# standalone.net
KiCad netlist of a schematic drawn in EAGLE
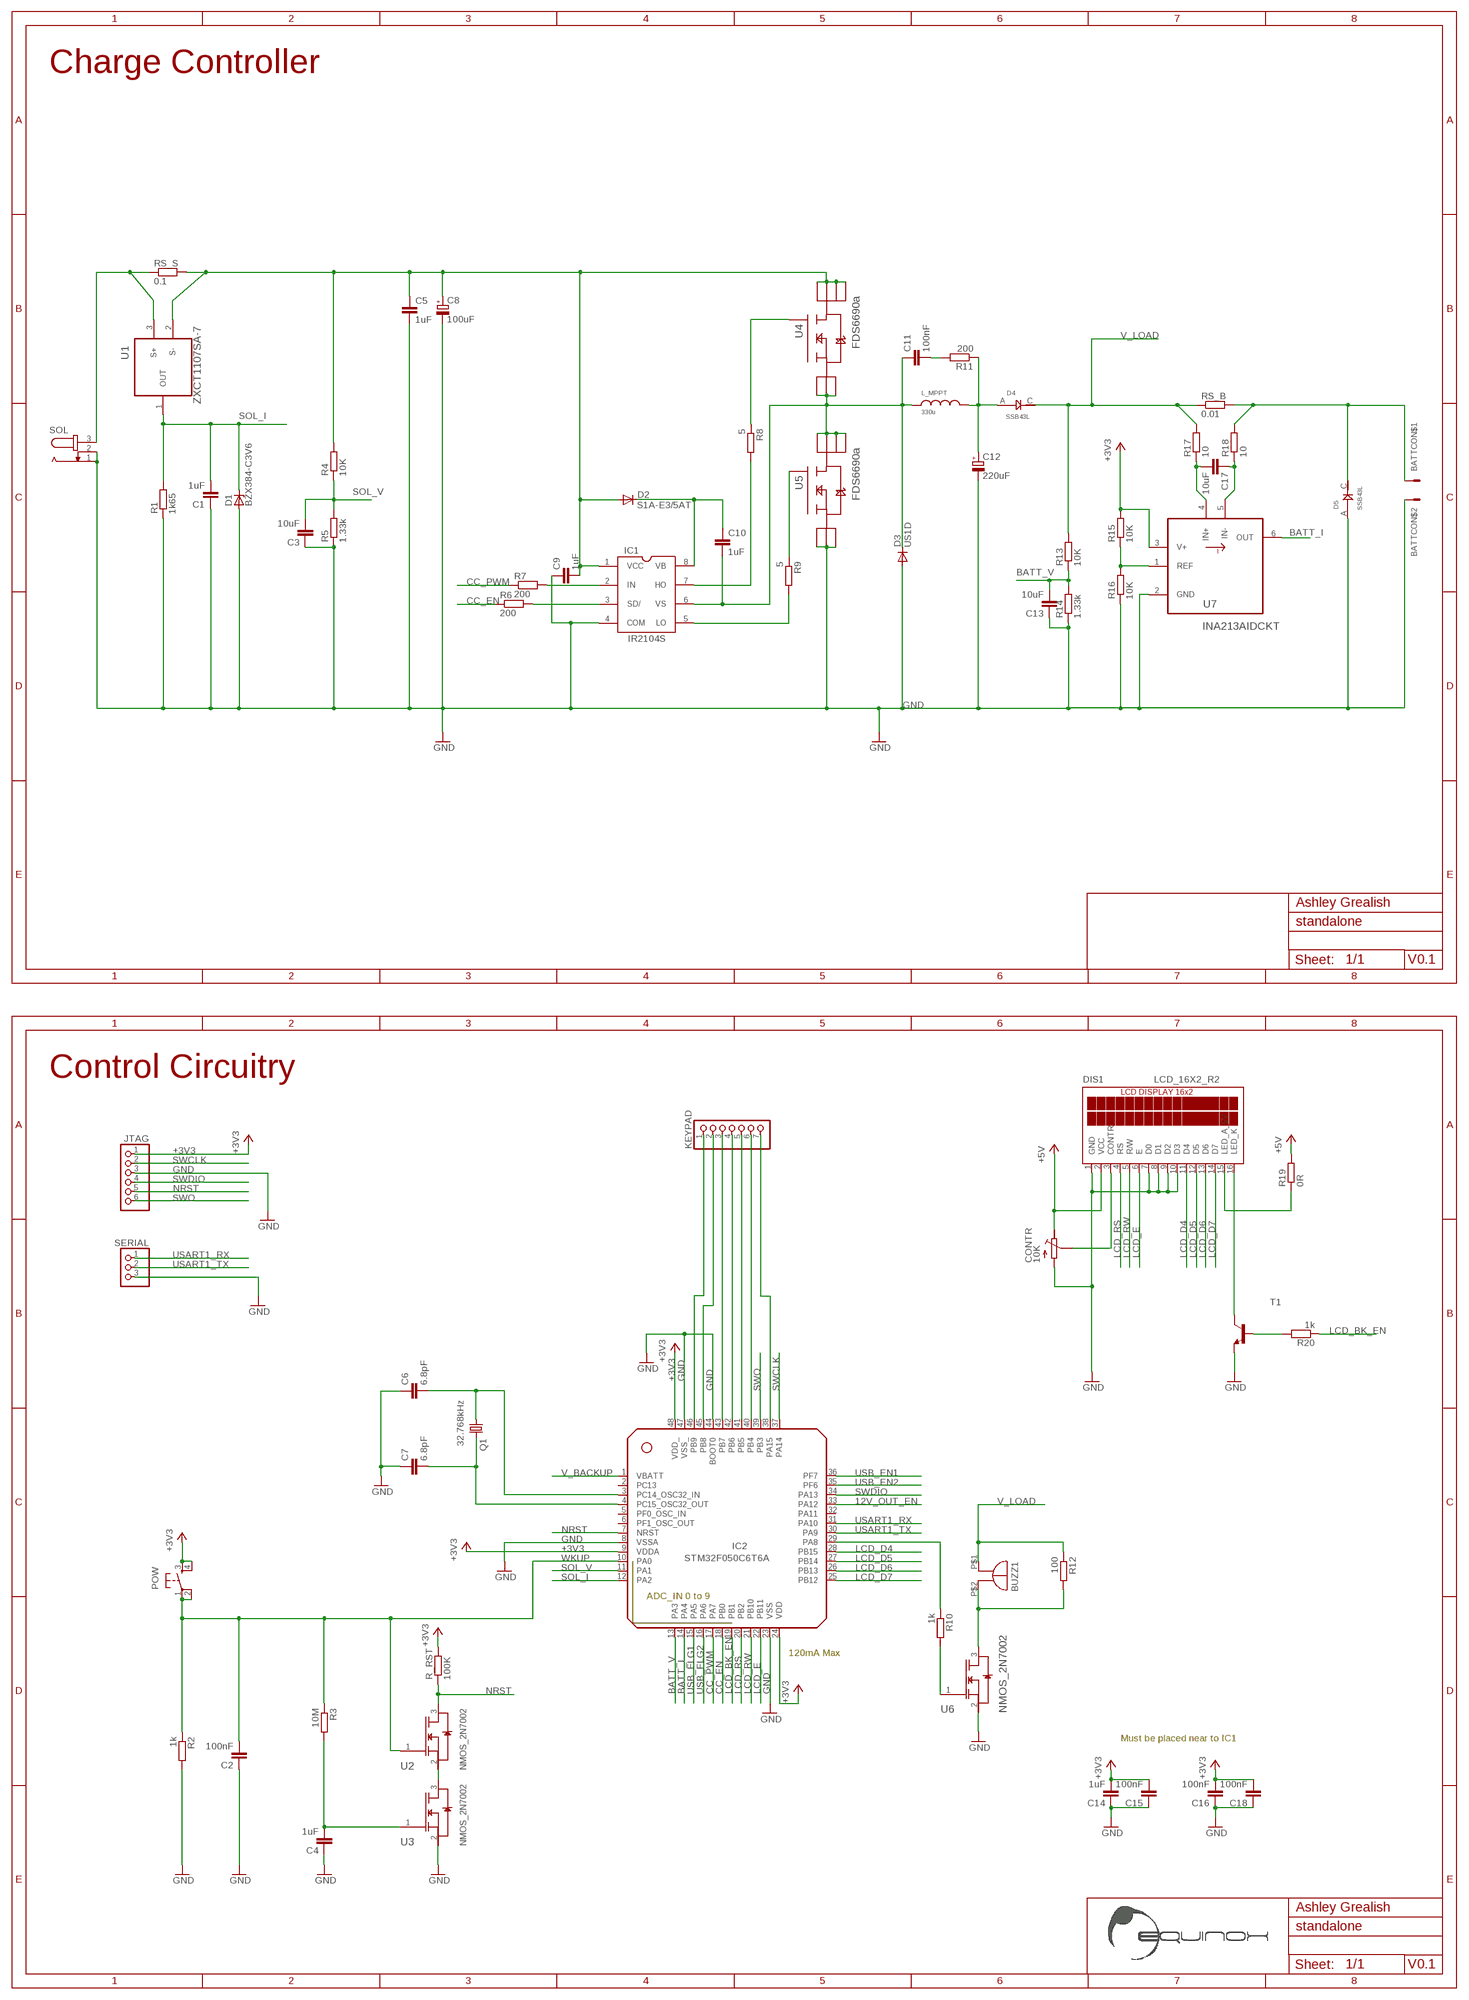
[diagram p0: schematic, sheet 1, part 1 of 2]
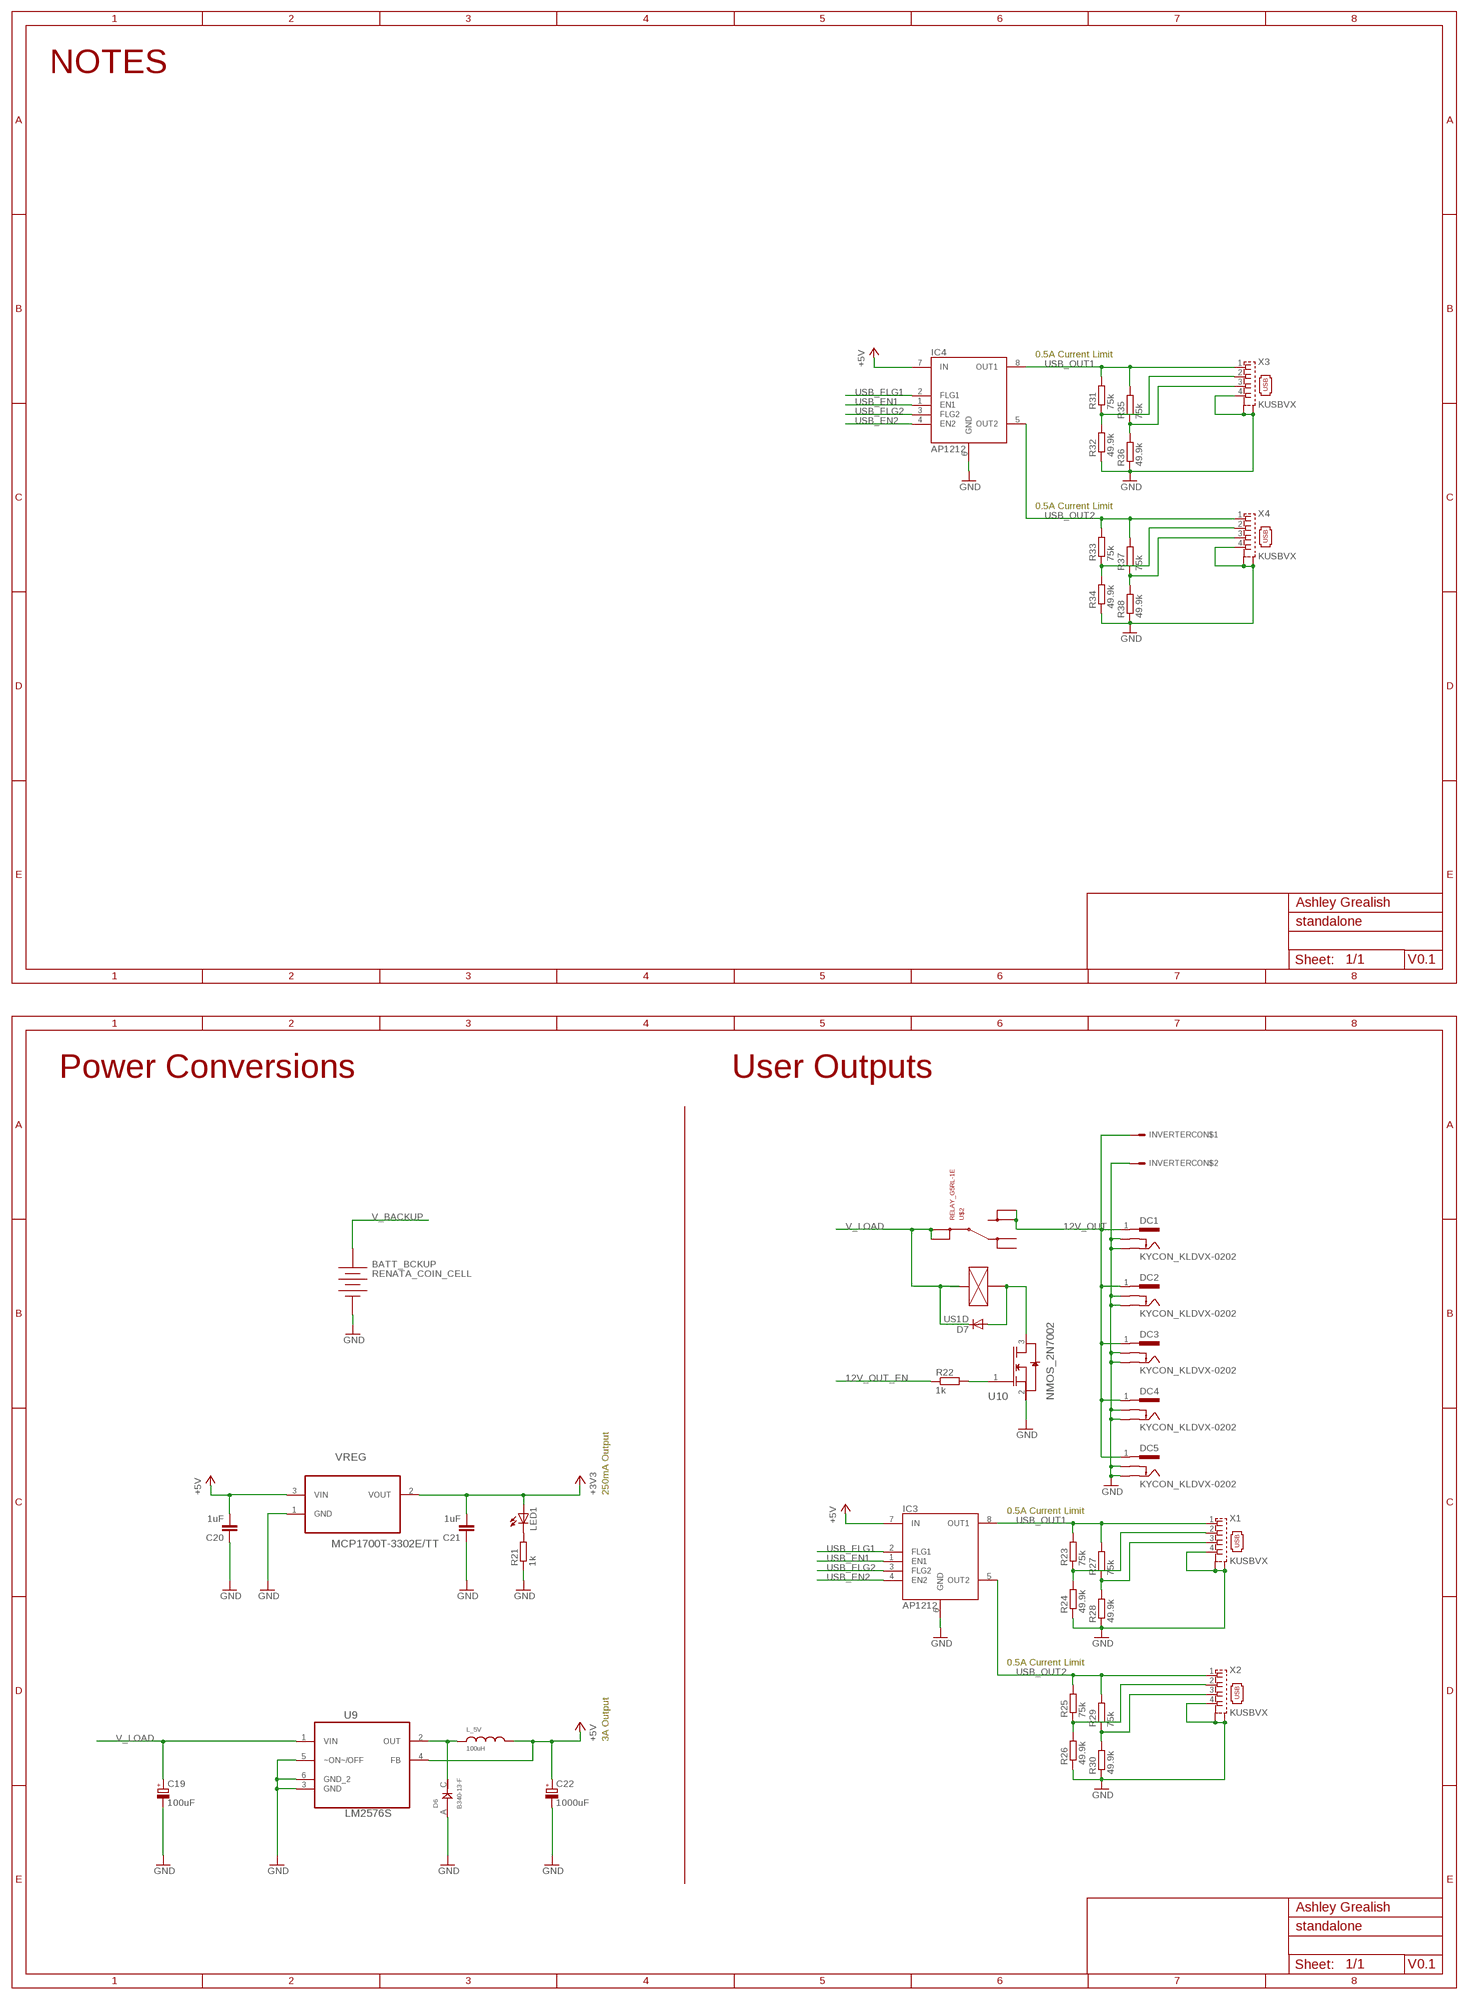
[diagram p1: schematic, sheet 1, part 2 of 2]

(export (version "E")
  (design (tool "Eeschema 10.0.6"))
  (components
    (comp (ref "BATT")
      (value "CON_MOLEX_39_29_1028")
      (footprint "eagle-import:MOLEX_39_29_1028")
      (fields (field (name "OC_FARNELL") "1012166"))
      (libsource (lib "eagle-import") (part "CON_MOLEX_39_29_1028"))
    )
    (comp (ref "BATT_BCKUP")
      (value "RENATA_COIN_CELL")
      (footprint "eagle-import:PANASONIC_CR2032_1298246")
      (libsource (lib "eagle-import") (part "PANASONIC_CR2032_1298246"))
    )
    (comp (ref "BUZZ1")
      (value "BUZZ_14MM")
      (footprint "eagle-import:BUZZ_14MM_5M_PINS")
      (libsource (lib "eagle-import") (part "BUZZ_14MM"))
    )
    (comp (ref "C1")
      (value "1uF")
      (footprint "eagle-import:C0805K")
      (libsource (lib "eagle-import") (part "C-EUC0805K"))
    )
    (comp (ref "C2")
      (value "100nF")
      (footprint "eagle-import:C0805K")
      (libsource (lib "eagle-import") (part "C-EUC0805K"))
    )
    (comp (ref "C3")
      (value "10uF")
      (footprint "eagle-import:C0805K")
      (libsource (lib "eagle-import") (part "C-EUC0805K"))
    )
    (comp (ref "C4")
      (value "1uF")
      (footprint "eagle-import:C0805K")
      (libsource (lib "eagle-import") (part "C-EUC0805K"))
    )
    (comp (ref "C5")
      (value "1uF")
      (footprint "eagle-import:C0805K")
      (libsource (lib "eagle-import") (part "C-EUC0805K"))
    )
    (comp (ref "C6")
      (value "6.8pF")
      (footprint "eagle-import:C0603K")
      (libsource (lib "eagle-import") (part "C-EUC0603K"))
    )
    (comp (ref "C7")
      (value "6.8pF")
      (footprint "eagle-import:C0603K")
      (libsource (lib "eagle-import") (part "C-EUC0603K"))
    )
    (comp (ref "C8")
      (value "100uF")
      (footprint "eagle-import:PANASONIC_E")
      (libsource (lib "eagle-import") (part "CPOL-EUE"))
    )
    (comp (ref "C9")
      (value "1uF")
      (footprint "eagle-import:C0805K")
      (libsource (lib "eagle-import") (part "C-EUC0805K"))
    )
    (comp (ref "C10")
      (value "1uF")
      (footprint "eagle-import:C0805K")
      (libsource (lib "eagle-import") (part "C-EUC0805K"))
    )
    (comp (ref "C11")
      (value "100nF")
      (footprint "eagle-import:C0805K")
      (libsource (lib "eagle-import") (part "C-EUC0805K"))
    )
    (comp (ref "C12")
      (value "220uF")
      (footprint "eagle-import:PANASONIC_F")
      (libsource (lib "eagle-import") (part "CPOL-EUF"))
    )
    (comp (ref "C13")
      (value "10uF")
      (footprint "eagle-import:C0805K")
      (libsource (lib "eagle-import") (part "C-EUC0805K"))
    )
    (comp (ref "C14")
      (value "1uF")
      (footprint "eagle-import:C0805K")
      (libsource (lib "eagle-import") (part "C-EUC0805K"))
    )
    (comp (ref "C15")
      (value "100nF")
      (footprint "eagle-import:C0805K")
      (libsource (lib "eagle-import") (part "C-EUC0805K"))
    )
    (comp (ref "C16")
      (value "100nF")
      (footprint "eagle-import:C0805K")
      (libsource (lib "eagle-import") (part "C-EUC0805K"))
    )
    (comp (ref "C17")
      (value "10uF")
      (footprint "eagle-import:C0805K")
      (libsource (lib "eagle-import") (part "C-EUC0805K"))
    )
    (comp (ref "C18")
      (value "100nF")
      (footprint "eagle-import:C0805K")
      (libsource (lib "eagle-import") (part "C-EUC0805K"))
    )
    (comp (ref "C19")
      (value "100uF")
      (footprint "eagle-import:PANASONIC_E")
      (libsource (lib "eagle-import") (part "CPOL-EUE"))
    )
    (comp (ref "C20")
      (value "1uF")
      (footprint "eagle-import:C0805K")
      (libsource (lib "eagle-import") (part "C-EUC0805K"))
    )
    (comp (ref "C21")
      (value "1uF")
      (footprint "eagle-import:C0805K")
      (libsource (lib "eagle-import") (part "C-EUC0805K"))
    )
    (comp (ref "C22")
      (value "1000uF")
      (footprint "eagle-import:PANASONIC_G")
      (libsource (lib "eagle-import") (part "CPOL-EUG"))
    )
    (comp (ref "CONTR")
      (value "10K")
      (footprint "eagle-import:R_TRIMM_RC33X")
      (libsource (lib "eagle-import") (part "R_TRIMM_TC33X"))
    )
    (comp (ref "D1")
      (value "BZX384-C3V6")
      (footprint "eagle-import:SOD323")
      (libsource (lib "eagle-import") (part "BZX384-C3V6"))
    )
    (comp (ref "D2")
      (value "S1A-E3/5AT")
      (footprint "eagle-import:DO-214AC")
      (libsource (lib "eagle-import") (part "DIODE-DO-214AC"))
    )
    (comp (ref "D3")
      (value "US1D")
      (footprint "eagle-import:DO-214AC")
      (libsource (lib "eagle-import") (part "DIODE-DO-214AC"))
    )
    (comp (ref "D4")
      (value "SSB43L")
      (footprint "eagle-import:DO214AA")
      (libsource (lib "eagle-import") (part "DIODE_SSB43L"))
    )
    (comp (ref "D5")
      (value "SSB43L")
      (footprint "eagle-import:DO214AA")
      (libsource (lib "eagle-import") (part "DIODE_SSB43L"))
    )
    (comp (ref "D6")
      (value "B340-13-F")
      (footprint "eagle-import:SMC")
      (libsource (lib "eagle-import") (part "DIODE_B340-13-F"))
    )
    (comp (ref "D7")
      (value "US1D")
      (footprint "eagle-import:DO-214AC")
      (libsource (lib "eagle-import") (part "DIODE-DO-214AC"))
    )
    (comp (ref "DC1")
      (value "KYCON_KLDVX-0202")
      (footprint "eagle-import:KYCON_KLVDX_2020_B")
      (libsource (lib "eagle-import") (part "KYCON_KLDVX-0202"))
    )
    (comp (ref "DC2")
      (value "KYCON_KLDVX-0202")
      (footprint "eagle-import:KYCON_KLVDX_2020_B")
      (libsource (lib "eagle-import") (part "KYCON_KLDVX-0202"))
    )
    (comp (ref "DC3")
      (value "KYCON_KLDVX-0202")
      (footprint "eagle-import:KYCON_KLVDX_2020_B")
      (libsource (lib "eagle-import") (part "KYCON_KLDVX-0202"))
    )
    (comp (ref "DC4")
      (value "KYCON_KLDVX-0202")
      (footprint "eagle-import:KYCON_KLVDX_2020_B")
      (libsource (lib "eagle-import") (part "KYCON_KLDVX-0202"))
    )
    (comp (ref "DC5")
      (value "KYCON_KLDVX-0202")
      (footprint "eagle-import:KYCON_KLVDX_2020_B")
      (libsource (lib "eagle-import") (part "KYCON_KLDVX-0202"))
    )
    (comp (ref "DIS1")
      (value "LCD_16X2_R2")
      (footprint "eagle-import:LCD_16X2_R2")
      (libsource (lib "eagle-import") (part "LCD_16X2_R2"))
    )
    (comp (ref "IC1")
      (value "IR2104S")
      (footprint "eagle-import:IR2104S")
      (libsource (lib "eagle-import") (part "IR2104S"))
    )
    (comp (ref "IC2")
      (value "STM32F050C6T6A")
      (footprint "eagle-import:LQFP48")
      (libsource (lib "eagle-import") (part "STM32F050C6T6A"))
    )
    (comp (ref "IC3")
      (value "AP1212")
      (footprint "eagle-import:SO8")
      (libsource (lib "eagle-import") (part "AP1212"))
    )
    (comp (ref "IC4")
      (value "AP1212")
      (footprint "eagle-import:SO8")
      (libsource (lib "eagle-import") (part "AP1212"))
    )
    (comp (ref "INVERTER")
      (value "CON_MOLEX_39_29_1028")
      (footprint "eagle-import:MOLEX_39_29_1028")
      (libsource (lib "eagle-import") (part "CON_MOLEX_39_29_1028"))
    )
    (comp (ref "JTAG")
      (value "PINHD-1X6")
      (footprint "eagle-import:1X06")
      (libsource (lib "eagle-import") (part "PINHD-1X6"))
    )
    (comp (ref "KEYPAD")
      (value "PINHD-1X7/90")
      (footprint "eagle-import:1X07_90")
      (libsource (lib "eagle-import") (part "PINHD-1X7/90"))
    )
    (comp (ref "LED1")
      (value "POW_3V3")
      (footprint "eagle-import:CHIPLED_0805")
      (libsource (lib "eagle-import") (part "LEDCHIPLED_0805"))
    )
    (comp (ref "L_5V")
      (value "100uH")
      (footprint "eagle-import:INDUC_BOURNS_SDR2207")
      (libsource (lib "eagle-import") (part "INDUC_BOURNES_SDR2207"))
    )
    (comp (ref "L_MPPT")
      (value "330u")
      (footprint "eagle-import:INDUC_MURATA_1433428C")
      (libsource (lib "eagle-import") (part "INDUC_MURATA_1433428C"))
    )
    (comp (ref "POW")
      (value "TAC_SWITCHPTH")
      (footprint "eagle-import:TACTILE-PTH")
      (libsource (lib "eagle-import") (part "TAC_SWITCHPTH"))
    )
    (comp (ref "Q1")
      (value "32.768kHz")
      (footprint "eagle-import:MC-306")
      (fields
        (field (name "MPN") "MC-306 60.0KHZ  100PPM ,12.5PF")
        (field (name "MPN_1") "MC-306")
        (field (name "OC_FARNELL") "1712823")
        (field (name "OC_NEWARK") "-")
      )
      (libsource (lib "eagle-import") (part "MC-306"))
    )
    (comp (ref "R1")
      (value "1k65")
      (footprint "eagle-import:M0805")
      (libsource (lib "eagle-import") (part "R-EU_M0805"))
    )
    (comp (ref "R2")
      (value "1k")
      (footprint "eagle-import:M0805")
      (libsource (lib "eagle-import") (part "resistor_R-EU_M0805"))
    )
    (comp (ref "R3")
      (value "10M")
      (footprint "eagle-import:M0805")
      (libsource (lib "eagle-import") (part "resistor_R-EU_M0805"))
    )
    (comp (ref "R4")
      (value "10K")
      (footprint "eagle-import:M0805")
      (libsource (lib "eagle-import") (part "R-EU_M0805"))
    )
    (comp (ref "R5")
      (value "1.33k")
      (footprint "eagle-import:M0805")
      (libsource (lib "eagle-import") (part "R-EU_M0805"))
    )
    (comp (ref "R6")
      (value "200")
      (footprint "eagle-import:M0805")
      (libsource (lib "eagle-import") (part "R-EU_M0805"))
    )
    (comp (ref "R7")
      (value "200")
      (footprint "eagle-import:M0805")
      (libsource (lib "eagle-import") (part "R-EU_M0805"))
    )
    (comp (ref "R8")
      (value "5")
      (footprint "eagle-import:M0805")
      (libsource (lib "eagle-import") (part "R-EU_M0805"))
    )
    (comp (ref "R9")
      (value "5")
      (footprint "eagle-import:M0805")
      (libsource (lib "eagle-import") (part "R-EU_M0805"))
    )
    (comp (ref "R10")
      (value "1k")
      (footprint "eagle-import:M0805")
      (libsource (lib "eagle-import") (part "resistor_R-EU_M0805"))
    )
    (comp (ref "R11")
      (value "200")
      (footprint "eagle-import:M0805")
      (libsource (lib "eagle-import") (part "R-EU_M0805"))
    )
    (comp (ref "R12")
      (value "100")
      (footprint "eagle-import:M0805")
      (libsource (lib "eagle-import") (part "resistor_R-EU_M0805"))
    )
    (comp (ref "R13")
      (value "10K")
      (footprint "eagle-import:M0805")
      (libsource (lib "eagle-import") (part "R-EU_M0805"))
    )
    (comp (ref "R14")
      (value "1.33k")
      (footprint "eagle-import:M0805")
      (libsource (lib "eagle-import") (part "R-EU_M0805"))
    )
    (comp (ref "R15")
      (value "10K")
      (footprint "eagle-import:M0805")
      (libsource (lib "eagle-import") (part "R-EU_M0805"))
    )
    (comp (ref "R16")
      (value "10K")
      (footprint "eagle-import:M0805")
      (libsource (lib "eagle-import") (part "R-EU_M0805"))
    )
    (comp (ref "R17")
      (value "10")
      (footprint "eagle-import:M0805")
      (libsource (lib "eagle-import") (part "R-EU_M0805"))
    )
    (comp (ref "R18")
      (value "10")
      (footprint "eagle-import:M0805")
      (libsource (lib "eagle-import") (part "R-EU_M0805"))
    )
    (comp (ref "R19")
      (value "0R")
      (footprint "eagle-import:M0805")
      (libsource (lib "eagle-import") (part "resistor_R-EU_M0805"))
    )
    (comp (ref "R20")
      (value "1k")
      (footprint "eagle-import:M0805")
      (libsource (lib "eagle-import") (part "resistor_R-EU_M0805"))
    )
    (comp (ref "R21")
      (value "1k")
      (footprint "eagle-import:M0805")
      (libsource (lib "eagle-import") (part "resistor_R-EU_M0805"))
    )
    (comp (ref "R22")
      (value "1k")
      (footprint "eagle-import:M0805")
      (libsource (lib "eagle-import") (part "R-EU_M0805"))
    )
    (comp (ref "R23")
      (value "75k")
      (footprint "eagle-import:M0805")
      (libsource (lib "eagle-import") (part "resistor_R-EU_M0805"))
    )
    (comp (ref "R24")
      (value "49.9k")
      (footprint "eagle-import:M0805")
      (libsource (lib "eagle-import") (part "resistor_R-EU_M0805"))
    )
    (comp (ref "R25")
      (value "75k")
      (footprint "eagle-import:M0805")
      (libsource (lib "eagle-import") (part "resistor_R-EU_M0805"))
    )
    (comp (ref "R26")
      (value "49.9k")
      (footprint "eagle-import:M0805")
      (libsource (lib "eagle-import") (part "resistor_R-EU_M0805"))
    )
    (comp (ref "R27")
      (value "75k")
      (footprint "eagle-import:M0805")
      (libsource (lib "eagle-import") (part "resistor_R-EU_M0805"))
    )
    (comp (ref "R28")
      (value "49.9k")
      (footprint "eagle-import:M0805")
      (libsource (lib "eagle-import") (part "resistor_R-EU_M0805"))
    )
    (comp (ref "R29")
      (value "75k")
      (footprint "eagle-import:M0805")
      (libsource (lib "eagle-import") (part "resistor_R-EU_M0805"))
    )
    (comp (ref "R30")
      (value "49.9k")
      (footprint "eagle-import:M0805")
      (libsource (lib "eagle-import") (part "resistor_R-EU_M0805"))
    )
    (comp (ref "R31")
      (value "75k")
      (footprint "eagle-import:M0805")
      (libsource (lib "eagle-import") (part "resistor_R-EU_M0805"))
    )
    (comp (ref "R32")
      (value "49.9k")
      (footprint "eagle-import:M0805")
      (libsource (lib "eagle-import") (part "resistor_R-EU_M0805"))
    )
    (comp (ref "R33")
      (value "75k")
      (footprint "eagle-import:M0805")
      (libsource (lib "eagle-import") (part "resistor_R-EU_M0805"))
    )
    (comp (ref "R34")
      (value "49.9k")
      (footprint "eagle-import:M0805")
      (libsource (lib "eagle-import") (part "resistor_R-EU_M0805"))
    )
    (comp (ref "R35")
      (value "75k")
      (footprint "eagle-import:M0805")
      (libsource (lib "eagle-import") (part "resistor_R-EU_M0805"))
    )
    (comp (ref "R36")
      (value "49.9k")
      (footprint "eagle-import:M0805")
      (libsource (lib "eagle-import") (part "resistor_R-EU_M0805"))
    )
    (comp (ref "R37")
      (value "75k")
      (footprint "eagle-import:M0805")
      (libsource (lib "eagle-import") (part "resistor_R-EU_M0805"))
    )
    (comp (ref "R38")
      (value "49.9k")
      (footprint "eagle-import:M0805")
      (libsource (lib "eagle-import") (part "resistor_R-EU_M0805"))
    )
    (comp (ref "RS_B")
      (value "0.01")
      (footprint "eagle-import:R2512")
      (libsource (lib "eagle-import") (part "R-EU_R2512"))
    )
    (comp (ref "RS_S")
      (value "0.1")
      (footprint "eagle-import:R2512")
      (libsource (lib "eagle-import") (part "R-EU_R2512"))
    )
    (comp (ref "R_RST")
      (value "100K")
      (footprint "eagle-import:M0805")
      (libsource (lib "eagle-import") (part "R-EU_M0805"))
    )
    (comp (ref "SERIAL")
      (value "PINHD-1X3")
      (footprint "eagle-import:1X03")
      (libsource (lib "eagle-import") (part "PINHD-1X3"))
    )
    (comp (ref "SOL")
      (value "JACK-PLUG0")
      (footprint "eagle-import:SPC4077")
      (libsource (lib "eagle-import") (part "JACK-PLUG0"))
    )
    (comp (ref "T1")
      (value "BC847B-NPN-SOT23-BEC")
      (footprint "eagle-import:SOT23-BEC")
      (libsource (lib "eagle-import") (part "-NPN-SOT23-BECBC847B"))
    )
    (comp (ref "U$1")
      (value "EQUINOX_LOGO_LARGE")
      (footprint "eagle-import:EQUINOX_LOGO_LARGE")
      (libsource (lib "eagle-import") (part "EQUINOX_LOGO_LARGE"))
    )
    (comp (ref "U$2")
      (value "RELAY_G5RL-1E")
      (footprint "eagle-import:G5RL-1E")
      (libsource (lib "eagle-import") (part "RELAY_G5RL-1E"))
    )
    (comp (ref "U1")
      (value "ZXCT1107SA-7")
      (footprint "eagle-import:SOT91P240X110-3N")
      (libsource (lib "eagle-import") (part "ZXCT1107SA-7"))
    )
    (comp (ref "U2")
      (value "NMOS_2N7002")
      (footprint "eagle-import:SOT103P240X110-3N")
      (fields
        (field (name "MPN") "2N7002-7-F")
        (field (name "MPN_1") "2N7002-7-F")
        (field (name "OC_FARNELL") "1713823")
        (field (name "OC_NEWARK") "25R5679")
        (field (name "PACKAGE") "SOT-23-3")
        (field (name "SUPPLIER") "DIODES INC.")
      )
      (libsource (lib "eagle-import") (part "NMOS_2N7002"))
    )
    (comp (ref "U3")
      (value "NMOS_2N7002")
      (footprint "eagle-import:SOT103P240X110-3N")
      (fields
        (field (name "MPN") "2N7002-7-F")
        (field (name "MPN_1") "2N7002-7-F")
        (field (name "OC_FARNELL") "1713823")
        (field (name "OC_NEWARK") "25R5679")
        (field (name "PACKAGE") "SOT-23-3")
        (field (name "SUPPLIER") "DIODES INC.")
      )
      (libsource (lib "eagle-import") (part "NMOS_2N7002"))
    )
    (comp (ref "U4")
      (value "FDS6690a")
      (footprint "eagle-import:SOIC127P600X175-8N")
      (fields (field (name "MPN") "DMS3016SSS-13") (field (name "OC_FARNELL") "9845275"))
      (libsource (lib "eagle-import") (part "DMS3016SSS-13"))
    )
    (comp (ref "U5")
      (value "FDS6690a")
      (footprint "eagle-import:SOIC127P600X175-8N")
      (fields (field (name "MPN") "DMS3016SSS-13") (field (name "OC_FARNELL") "9845275 "))
      (libsource (lib "eagle-import") (part "DMS3016SSS-13"))
    )
    (comp (ref "U6")
      (value "NMOS_2N7002")
      (footprint "eagle-import:SOT103P240X110-3N")
      (fields
        (field (name "MPN") "2N7002-7-F")
        (field (name "MPN_1") "2N7002-7-F")
        (field (name "OC_FARNELL") "1713823")
        (field (name "OC_NEWARK") "25R5679")
        (field (name "PACKAGE") "SOT-23-3")
        (field (name "SUPPLIER") "DIODES INC.")
      )
      (libsource (lib "eagle-import") (part "NMOS_2N7002"))
    )
    (comp (ref "U7")
      (value "INA213AIDCKT")
      (footprint "eagle-import:SOT65P210X110-6N")
      (libsource (lib "eagle-import") (part "INA213AIDCKT"))
    )
    (comp (ref "U9")
      (value "LM2576S")
      (footprint "eagle-import:TO263-5")
      (libsource (lib "eagle-import") (part "LM2576S"))
    )
    (comp (ref "U10")
      (value "NMOS_2N7002")
      (footprint "eagle-import:SOT103P240X110-3N")
      (fields (field (name "MPN") "2N7002-7-F"))
      (libsource (lib "eagle-import") (part "NMOS_2N7002"))
    )
    (comp (ref "VREG")
      (value "MCP1700T-3302E/TT")
      (footprint "eagle-import:SOT95P237X112-3N")
      (libsource (lib "eagle-import") (part "MCP1700T-3302E/TT"))
    )
    (comp (ref "X1")
      (value "KUSBVX")
      (footprint "eagle-import:KUSBVX")
      (libsource (lib "eagle-import") (part "KUSBVX"))
    )
    (comp (ref "X2")
      (value "KUSBVX")
      (footprint "eagle-import:KUSBVX")
      (libsource (lib "eagle-import") (part "KUSBVX"))
    )
    (comp (ref "X3")
      (value "KUSBVX")
      (footprint "eagle-import:KUSBVX")
      (libsource (lib "eagle-import") (part "KUSBVX"))
    )
    (comp (ref "X4")
      (value "KUSBVX")
      (footprint "eagle-import:KUSBVX")
      (libsource (lib "eagle-import") (part "KUSBVX"))
    )
  )
  (nets
    (net (code "1") (name "+3V3") (class "Default")
      (node (ref "C14") (pin "2") (pinfunction "2_2") (pintype "passive"))
      (node (ref "C15") (pin "2") (pinfunction "2_2") (pintype "passive"))
      (node (ref "C16") (pin "2") (pinfunction "2_2") (pintype "passive"))
      (node (ref "C18") (pin "2") (pinfunction "2_2") (pintype "passive"))
      (node (ref "C21") (pin "2") (pinfunction "2_2") (pintype "passive"))
      (node (ref "IC2") (pin "24") (pinfunction "VDD_24") (pintype "power_in"))
      (node (ref "IC2") (pin "48") (pinfunction "VDD__48") (pintype "power_in"))
      (node (ref "IC2") (pin "9") (pinfunction "VDDA_9") (pintype "bidirectional"))
      (node (ref "JTAG") (pin "1") (pinfunction "1_1") (pintype "passive"))
      (node (ref "LED1") (pin "A") (pinfunction "A_A") (pintype "passive"))
      (node (ref "POW") (pin "3") (pinfunction "3_3") (pintype "passive"))
      (node (ref "POW") (pin "4") (pinfunction "4_4") (pintype "passive"))
      (node (ref "R15") (pin "2") (pinfunction "2_2") (pintype "passive"))
      (node (ref "R_RST") (pin "2") (pinfunction "2_2") (pintype "passive"))
      (node (ref "U7") (pin "3") (pinfunction "V+_3") (pintype "power_in"))
      (node (ref "VREG") (pin "2") (pinfunction "VOUT_2") (pintype "output"))
    )
    (net (code "2") (name "+5V") (class "Default")
      (node (ref "C20") (pin "2") (pinfunction "2_2") (pintype "passive"))
      (node (ref "C22") (pin "+") (pinfunction "+_+") (pintype "passive"))
      (node (ref "CONTR") (pin "CW") (pinfunction "A_CW") (pintype "passive"))
      (node (ref "DIS1") (pin "2") (pinfunction "VCC_2") (pintype "power_in"))
      (node (ref "IC3") (pin "7") (pinfunction "IN_7") (pintype "bidirectional"))
      (node (ref "IC4") (pin "7") (pinfunction "IN_7") (pintype "bidirectional"))
      (node (ref "L_5V") (pin "P$2") (pinfunction "P$2_P$2") (pintype "bidirectional"))
      (node (ref "R19") (pin "2") (pinfunction "2_2") (pintype "passive"))
      (node (ref "U9") (pin "4") (pinfunction "FB_4") (pintype "bidirectional"))
      (node (ref "VREG") (pin "3") (pinfunction "VIN_3") (pintype "input"))
    )
    (net (code "3") (name "/12V_OUT") (class "Default")
      (node (ref "DC1") (pin "1") (pinfunction "PAD1_1") (pintype "passive"))
      (node (ref "DC2") (pin "1") (pinfunction "PAD1_1") (pintype "passive"))
      (node (ref "DC3") (pin "1") (pinfunction "PAD1_1") (pintype "passive"))
      (node (ref "DC4") (pin "1") (pinfunction "PAD1_1") (pintype "passive"))
      (node (ref "DC5") (pin "1") (pinfunction "PAD1_1") (pintype "passive"))
      (node (ref "INVERTER") (pin "P$1") (pinfunction "S_P$1") (pintype "passive"))
      (node (ref "U$2") (pin "NO@1") (pinfunction "NO_NO@1") (pintype "bidirectional"))
      (node (ref "U$2") (pin "NO@2") (pinfunction "NO_NO@2") (pintype "bidirectional"))
    )
    (net (code "4") (name "/12V_OUT_EN") (class "Default")
      (node (ref "IC2") (pin "33") (pinfunction "PA12_33") (pintype "bidirectional"))
      (node (ref "R22") (pin "1") (pinfunction "1_1") (pintype "passive"))
    )
    (net (code "5") (name "/BATT_I") (class "Default")
      (node (ref "IC2") (pin "14") (pinfunction "PA4_14") (pintype "bidirectional"))
      (node (ref "U7") (pin "6") (pinfunction "OUT_6") (pintype "output"))
    )
    (net (code "6") (name "/BATT_V") (class "Default")
      (node (ref "C13") (pin "2") (pinfunction "2_2") (pintype "passive"))
      (node (ref "IC2") (pin "13") (pinfunction "PA3_13") (pintype "bidirectional"))
      (node (ref "R13") (pin "1") (pinfunction "1_1") (pintype "passive"))
      (node (ref "R14") (pin "2") (pinfunction "2_2") (pintype "passive"))
    )
    (net (code "7") (name "/CC_EN") (class "Default")
      (node (ref "IC2") (pin "18") (pinfunction "PB0_18") (pintype "bidirectional"))
      (node (ref "R6") (pin "1") (pinfunction "1_1") (pintype "passive"))
    )
    (net (code "8") (name "/CC_PWM") (class "Default")
      (node (ref "IC2") (pin "17") (pinfunction "PA7_17") (pintype "bidirectional"))
      (node (ref "R7") (pin "1") (pinfunction "1_1") (pintype "passive"))
    )
    (net (code "9") (name "/LCD_BK_EN") (class "Default")
      (node (ref "IC2") (pin "19") (pinfunction "PB1_19") (pintype "bidirectional"))
      (node (ref "R20") (pin "1") (pinfunction "1_1") (pintype "passive"))
    )
    (net (code "10") (name "/LCD_D4") (class "Default")
      (node (ref "DIS1") (pin "11") (pinfunction "D4_11") (pintype "input"))
      (node (ref "IC2") (pin "28") (pinfunction "PB15_28") (pintype "bidirectional"))
    )
    (net (code "11") (name "/LCD_D5") (class "Default")
      (node (ref "DIS1") (pin "12") (pinfunction "D5_12") (pintype "input"))
      (node (ref "IC2") (pin "27") (pinfunction "PB14_27") (pintype "bidirectional"))
    )
    (net (code "12") (name "/LCD_D6") (class "Default")
      (node (ref "DIS1") (pin "13") (pinfunction "D6_13") (pintype "input"))
      (node (ref "IC2") (pin "26") (pinfunction "PB13_26") (pintype "bidirectional"))
    )
    (net (code "13") (name "/LCD_D7") (class "Default")
      (node (ref "DIS1") (pin "14") (pinfunction "D7_14") (pintype "input"))
      (node (ref "IC2") (pin "25") (pinfunction "PB12_25") (pintype "bidirectional"))
    )
    (net (code "14") (name "/LCD_E") (class "Default")
      (node (ref "DIS1") (pin "6") (pinfunction "E_6") (pintype "input"))
      (node (ref "IC2") (pin "22") (pinfunction "PB11_22") (pintype "bidirectional"))
    )
    (net (code "15") (name "/LCD_RS") (class "Default")
      (node (ref "DIS1") (pin "4") (pinfunction "RS_4") (pintype "input"))
      (node (ref "IC2") (pin "20") (pinfunction "PB2_20") (pintype "bidirectional"))
    )
    (net (code "16") (name "/LCD_RW") (class "Default")
      (node (ref "DIS1") (pin "5") (pinfunction "R/W_5") (pintype "input"))
      (node (ref "IC2") (pin "21") (pinfunction "PB10_21") (pintype "bidirectional"))
    )
    (net (code "17") (name "/NRST") (class "Default")
      (node (ref "IC2") (pin "7") (pinfunction "NRST_7") (pintype "bidirectional"))
      (node (ref "JTAG") (pin "5") (pinfunction "5_5") (pintype "passive"))
      (node (ref "R_RST") (pin "1") (pinfunction "1_1") (pintype "passive"))
      (node (ref "U2") (pin "3") (pinfunction "D_3") (pintype "output"))
    )
    (net (code "18") (name "/SOL_I") (class "Default")
      (node (ref "C1") (pin "2") (pinfunction "2_2") (pintype "passive"))
      (node (ref "D1") (pin "C") (pinfunction "C_C") (pintype "passive"))
      (node (ref "IC2") (pin "12") (pinfunction "PA2_12") (pintype "bidirectional"))
      (node (ref "R1") (pin "2") (pinfunction "2_2") (pintype "passive"))
      (node (ref "U1") (pin "1") (pinfunction "OUT_1") (pintype "output"))
    )
    (net (code "19") (name "/SOL_V") (class "Default")
      (node (ref "C3") (pin "2") (pinfunction "2_2") (pintype "passive"))
      (node (ref "IC2") (pin "11") (pinfunction "PA1_11") (pintype "bidirectional"))
      (node (ref "R4") (pin "1") (pinfunction "1_1") (pintype "passive"))
      (node (ref "R5") (pin "2") (pinfunction "2_2") (pintype "passive"))
    )
    (net (code "20") (name "/SWCLK") (class "Default")
      (node (ref "IC2") (pin "37") (pinfunction "PA14_37") (pintype "bidirectional"))
      (node (ref "JTAG") (pin "2") (pinfunction "2_2") (pintype "passive"))
    )
    (net (code "21") (name "/SWDIO") (class "Default")
      (node (ref "IC2") (pin "34") (pinfunction "PA13_34") (pintype "bidirectional"))
      (node (ref "JTAG") (pin "4") (pinfunction "4_4") (pintype "passive"))
    )
    (net (code "22") (name "/SWO") (class "Default")
      (node (ref "IC2") (pin "39") (pinfunction "PB3_39") (pintype "bidirectional"))
      (node (ref "JTAG") (pin "6") (pinfunction "6_6") (pintype "passive"))
    )
    (net (code "23") (name "/USART1_RX") (class "Default")
      (node (ref "IC2") (pin "31") (pinfunction "PA10_31") (pintype "bidirectional"))
      (node (ref "SERIAL") (pin "1") (pinfunction "1_1") (pintype "passive"))
    )
    (net (code "24") (name "/USART1_TX") (class "Default")
      (node (ref "IC2") (pin "30") (pinfunction "PA9_30") (pintype "bidirectional"))
      (node (ref "SERIAL") (pin "2") (pinfunction "2_2") (pintype "passive"))
    )
    (net (code "25") (name "/USB_EN1") (class "Default")
      (node (ref "IC2") (pin "36") (pinfunction "PF7_36") (pintype "bidirectional"))
      (node (ref "IC3") (pin "1") (pinfunction "EN1_1") (pintype "bidirectional"))
      (node (ref "IC4") (pin "1") (pinfunction "EN1_1") (pintype "bidirectional"))
    )
    (net (code "26") (name "/USB_EN2") (class "Default")
      (node (ref "IC2") (pin "35") (pinfunction "PF6_35") (pintype "bidirectional"))
      (node (ref "IC3") (pin "4") (pinfunction "EN2_4") (pintype "bidirectional"))
      (node (ref "IC4") (pin "4") (pinfunction "EN2_4") (pintype "bidirectional"))
    )
    (net (code "27") (name "/USB_FLG1") (class "Default")
      (node (ref "IC2") (pin "15") (pinfunction "PA5_15") (pintype "bidirectional"))
      (node (ref "IC3") (pin "2") (pinfunction "FLG1_2") (pintype "bidirectional"))
      (node (ref "IC4") (pin "2") (pinfunction "FLG1_2") (pintype "bidirectional"))
    )
    (net (code "28") (name "/USB_FLG2") (class "Default")
      (node (ref "IC2") (pin "16") (pinfunction "PA6_16") (pintype "bidirectional"))
      (node (ref "IC3") (pin "3") (pinfunction "FLG2_3") (pintype "bidirectional"))
      (node (ref "IC4") (pin "3") (pinfunction "FLG2_3") (pintype "bidirectional"))
    )
    (net (code "29") (name "/USB_OUT1") (class "Default")
      (node (ref "IC3") (pin "8") (pinfunction "OUT1_8") (pintype "bidirectional"))
      (node (ref "IC4") (pin "8") (pinfunction "OUT1_8") (pintype "bidirectional"))
      (node (ref "R23") (pin "2") (pinfunction "2_2") (pintype "passive"))
      (node (ref "R27") (pin "2") (pinfunction "2_2") (pintype "passive"))
      (node (ref "R31") (pin "2") (pinfunction "2_2") (pintype "passive"))
      (node (ref "R35") (pin "2") (pinfunction "2_2") (pintype "passive"))
      (node (ref "X1") (pin "1") (pinfunction "1_1") (pintype "passive"))
      (node (ref "X3") (pin "1") (pinfunction "1_1") (pintype "passive"))
    )
    (net (code "30") (name "/USB_OUT2") (class "Default")
      (node (ref "IC3") (pin "5") (pinfunction "OUT2_5") (pintype "bidirectional"))
      (node (ref "IC4") (pin "5") (pinfunction "OUT2_5") (pintype "bidirectional"))
      (node (ref "R25") (pin "2") (pinfunction "2_2") (pintype "passive"))
      (node (ref "R29") (pin "2") (pinfunction "2_2") (pintype "passive"))
      (node (ref "R33") (pin "2") (pinfunction "2_2") (pintype "passive"))
      (node (ref "R37") (pin "2") (pinfunction "2_2") (pintype "passive"))
      (node (ref "X2") (pin "1") (pinfunction "1_1") (pintype "passive"))
      (node (ref "X4") (pin "1") (pinfunction "1_1") (pintype "passive"))
    )
    (net (code "31") (name "/V_BACKUP") (class "Default")
      (node (ref "BATT_BCKUP") (pin "P+") (pinfunction "POS_P+") (pintype "bidirectional"))
      (node (ref "IC2") (pin "1") (pinfunction "VBATT_1") (pintype "bidirectional"))
    )
    (net (code "32") (name "/V_LOAD") (class "Default")
      (node (ref "BUZZ1") (pin "P$1") (pinfunction "+_P$1") (pintype "passive"))
      (node (ref "C19") (pin "+") (pinfunction "+_+") (pintype "passive"))
      (node (ref "D4") (pin "C") (pinfunction "CATHODE_C") (pintype "bidirectional"))
      (node (ref "D7") (pin "C") (pinfunction "C_C") (pintype "passive"))
      (node (ref "R12") (pin "1") (pinfunction "1_1") (pintype "passive"))
      (node (ref "R13") (pin "2") (pinfunction "2_2") (pintype "passive"))
      (node (ref "R17") (pin "2") (pinfunction "2_2") (pintype "passive"))
      (node (ref "RS_B") (pin "1") (pinfunction "1_1") (pintype "passive"))
      (node (ref "U$2") (pin "COM@1") (pinfunction "COM_COM@1") (pintype "bidirectional"))
      (node (ref "U$2") (pin "COM@2") (pinfunction "COM_COM@2") (pintype "bidirectional"))
      (node (ref "U9") (pin "1") (pinfunction "VIN_1") (pintype "input"))
    )
    (net (code "33") (name "/WKUP") (class "Default")
      (node (ref "C2") (pin "2") (pinfunction "2_2") (pintype "passive"))
      (node (ref "IC2") (pin "10") (pinfunction "PA0_10") (pintype "bidirectional"))
      (node (ref "POW") (pin "1") (pinfunction "1_1") (pintype "passive"))
      (node (ref "POW") (pin "2") (pinfunction "2_2") (pintype "passive"))
      (node (ref "R2") (pin "1") (pinfunction "1_1") (pintype "passive"))
      (node (ref "R3") (pin "1") (pinfunction "1_1") (pintype "passive"))
      (node (ref "U2") (pin "1") (pinfunction "G_1") (pintype "input"))
    )
    (net (code "34") (name "GND") (class "Default")
      (node (ref "BATT") (pin "P$2") (pinfunction "S_P$2") (pintype "passive"))
      (node (ref "BATT_BCKUP") (pin "P-") (pinfunction "NEG_P-") (pintype "bidirectional"))
      (node (ref "C1") (pin "1") (pinfunction "1_1") (pintype "passive"))
      (node (ref "C12") (pin "-") (pinfunction "-_-") (pintype "passive"))
      (node (ref "C13") (pin "1") (pinfunction "1_1") (pintype "passive"))
      (node (ref "C14") (pin "1") (pinfunction "1_1") (pintype "passive"))
      (node (ref "C15") (pin "1") (pinfunction "1_1") (pintype "passive"))
      (node (ref "C16") (pin "1") (pinfunction "1_1") (pintype "passive"))
      (node (ref "C18") (pin "1") (pinfunction "1_1") (pintype "passive"))
      (node (ref "C19") (pin "-") (pinfunction "-_-") (pintype "passive"))
      (node (ref "C2") (pin "1") (pinfunction "1_1") (pintype "passive"))
      (node (ref "C20") (pin "1") (pinfunction "1_1") (pintype "passive"))
      (node (ref "C21") (pin "1") (pinfunction "1_1") (pintype "passive"))
      (node (ref "C22") (pin "-") (pinfunction "-_-") (pintype "passive"))
      (node (ref "C3") (pin "1") (pinfunction "1_1") (pintype "passive"))
      (node (ref "C4") (pin "1") (pinfunction "1_1") (pintype "passive"))
      (node (ref "C5") (pin "2") (pinfunction "2_2") (pintype "passive"))
      (node (ref "C6") (pin "1") (pinfunction "1_1") (pintype "passive"))
      (node (ref "C7") (pin "1") (pinfunction "1_1") (pintype "passive"))
      (node (ref "C8") (pin "-") (pinfunction "-_-") (pintype "passive"))
      (node (ref "C9") (pin "1") (pinfunction "1_1") (pintype "passive"))
      (node (ref "CONTR") (pin "CCW") (pinfunction "E_CCW") (pintype "passive"))
      (node (ref "D1") (pin "A") (pinfunction "A_A") (pintype "passive"))
      (node (ref "D3") (pin "A") (pinfunction "A_A") (pintype "passive"))
      (node (ref "D5") (pin "A") (pinfunction "ANODE_A") (pintype "bidirectional"))
      (node (ref "D6") (pin "A") (pinfunction "ANODE_A") (pintype "bidirectional"))
      (node (ref "DC1") (pin "2") (pinfunction "PAD2_2") (pintype "passive"))
      (node (ref "DC1") (pin "3") (pinfunction "PAD3_3") (pintype "passive"))
      (node (ref "DC2") (pin "2") (pinfunction "PAD2_2") (pintype "passive"))
      (node (ref "DC2") (pin "3") (pinfunction "PAD3_3") (pintype "passive"))
      (node (ref "DC3") (pin "2") (pinfunction "PAD2_2") (pintype "passive"))
      (node (ref "DC3") (pin "3") (pinfunction "PAD3_3") (pintype "passive"))
      (node (ref "DC4") (pin "2") (pinfunction "PAD2_2") (pintype "passive"))
      (node (ref "DC4") (pin "3") (pinfunction "PAD3_3") (pintype "passive"))
      (node (ref "DC5") (pin "2") (pinfunction "PAD2_2") (pintype "passive"))
      (node (ref "DC5") (pin "3") (pinfunction "PAD3_3") (pintype "passive"))
      (node (ref "DIS1") (pin "1") (pinfunction "GND_1") (pintype "power_in"))
      (node (ref "DIS1") (pin "10") (pinfunction "D3_10") (pintype "input"))
      (node (ref "DIS1") (pin "7") (pinfunction "D0_7") (pintype "input"))
      (node (ref "DIS1") (pin "8") (pinfunction "D1_8") (pintype "input"))
      (node (ref "DIS1") (pin "9") (pinfunction "D2_9") (pintype "input"))
      (node (ref "IC1") (pin "4") (pinfunction "COM_4") (pintype "bidirectional"))
      (node (ref "IC2") (pin "23") (pinfunction "VSS_23") (pintype "power_in"))
      (node (ref "IC2") (pin "44") (pinfunction "BOOT0_44") (pintype "bidirectional"))
      (node (ref "IC2") (pin "47") (pinfunction "VSS__47") (pintype "power_in"))
      (node (ref "IC2") (pin "8") (pinfunction "VSSA_8") (pintype "bidirectional"))
      (node (ref "IC3") (pin "6") (pinfunction "GND_6") (pintype "power_in"))
      (node (ref "IC4") (pin "6") (pinfunction "GND_6") (pintype "power_in"))
      (node (ref "INVERTER") (pin "P$2") (pinfunction "S_P$2") (pintype "passive"))
      (node (ref "JTAG") (pin "3") (pinfunction "3_3") (pintype "passive"))
      (node (ref "R1") (pin "1") (pinfunction "1_1") (pintype "passive"))
      (node (ref "R14") (pin "1") (pinfunction "1_1") (pintype "passive"))
      (node (ref "R16") (pin "1") (pinfunction "1_1") (pintype "passive"))
      (node (ref "R2") (pin "2") (pinfunction "2_2") (pintype "passive"))
      (node (ref "R21") (pin "1") (pinfunction "1_1") (pintype "passive"))
      (node (ref "R24") (pin "1") (pinfunction "1_1") (pintype "passive"))
      (node (ref "R26") (pin "1") (pinfunction "1_1") (pintype "passive"))
      (node (ref "R28") (pin "1") (pinfunction "1_1") (pintype "passive"))
      (node (ref "R30") (pin "1") (pinfunction "1_1") (pintype "passive"))
      (node (ref "R32") (pin "1") (pinfunction "1_1") (pintype "passive"))
      (node (ref "R34") (pin "1") (pinfunction "1_1") (pintype "passive"))
      (node (ref "R36") (pin "1") (pinfunction "1_1") (pintype "passive"))
      (node (ref "R38") (pin "1") (pinfunction "1_1") (pintype "passive"))
      (node (ref "R5") (pin "1") (pinfunction "1_1") (pintype "passive"))
      (node (ref "SERIAL") (pin "3") (pinfunction "3_3") (pintype "passive"))
      (node (ref "SOL") (pin "1") (pinfunction "1_1") (pintype "passive"))
      (node (ref "SOL") (pin "2") (pinfunction "2_2") (pintype "passive"))
      (node (ref "T1") (pin "E") (pinfunction "E_E") (pintype "passive"))
      (node (ref "U10") (pin "2") (pinfunction "S_2") (pintype "passive"))
      (node (ref "U3") (pin "2") (pinfunction "S_2") (pintype "passive"))
      (node (ref "U5") (pin "1") (pinfunction "S_2_1") (pintype "passive"))
      (node (ref "U5") (pin "2") (pinfunction "S_3_2") (pintype "passive"))
      (node (ref "U5") (pin "3") (pinfunction "S_3") (pintype "passive"))
      (node (ref "U6") (pin "2") (pinfunction "S_2") (pintype "passive"))
      (node (ref "U7") (pin "2") (pinfunction "GND_2") (pintype "passive"))
      (node (ref "U9") (pin "3") (pinfunction "GND_3") (pintype "passive"))
      (node (ref "U9") (pin "5") (pinfunction "~{ON}/OFF_5") (pintype "passive"))
      (node (ref "U9") (pin "6") (pinfunction "GND_2_6") (pintype "passive"))
      (node (ref "VREG") (pin "1") (pinfunction "GND_1") (pintype "passive"))
      (node (ref "X1") (pin "4") (pinfunction "4_4") (pintype "passive"))
      (node (ref "X1") (pin "M1") (pinfunction "S1_M1") (pintype "passive"))
      (node (ref "X1") (pin "M2") (pinfunction "S2_M2") (pintype "passive"))
      (node (ref "X2") (pin "4") (pinfunction "4_4") (pintype "passive"))
      (node (ref "X2") (pin "M1") (pinfunction "S1_M1") (pintype "passive"))
      (node (ref "X2") (pin "M2") (pinfunction "S2_M2") (pintype "passive"))
      (node (ref "X3") (pin "4") (pinfunction "4_4") (pintype "passive"))
      (node (ref "X3") (pin "M1") (pinfunction "S1_M1") (pintype "passive"))
      (node (ref "X3") (pin "M2") (pinfunction "S2_M2") (pintype "passive"))
      (node (ref "X4") (pin "4") (pinfunction "4_4") (pintype "passive"))
      (node (ref "X4") (pin "M1") (pinfunction "S1_M1") (pintype "passive"))
      (node (ref "X4") (pin "M2") (pinfunction "S2_M2") (pintype "passive"))
    )
    (net (code "35") (name "Net-(BATTA-S)") (class "Default")
      (node (ref "BATT") (pin "P$1") (pinfunction "S_P$1") (pintype "passive"))
      (node (ref "D5") (pin "C") (pinfunction "CATHODE_C") (pintype "bidirectional"))
      (node (ref "R18") (pin "2") (pinfunction "2_2") (pintype "passive"))
      (node (ref "RS_B") (pin "2") (pinfunction "2_2") (pintype "passive"))
    )
    (net (code "36") (name "Net-(BUZZ1--)") (class "Default")
      (node (ref "BUZZ1") (pin "P$2") (pinfunction "-_P$2") (pintype "passive"))
      (node (ref "R12") (pin "2") (pinfunction "2_2") (pintype "passive"))
      (node (ref "U6") (pin "3") (pinfunction "D_3") (pintype "output"))
    )
    (net (code "37") (name "Net-(C11-Pad2)") (class "Default")
      (node (ref "C11") (pin "2") (pinfunction "2_2") (pintype "passive"))
      (node (ref "R11") (pin "2") (pinfunction "2_2") (pintype "passive"))
    )
    (net (code "38") (name "Net-(CONTR-S)") (class "Default")
      (node (ref "CONTR") (pin "WIPE") (pinfunction "S_WIPE") (pintype "passive"))
      (node (ref "DIS1") (pin "3") (pinfunction "CONTR_3") (pintype "input"))
    )
    (net (code "39") (name "Net-(D4-ANODE)") (class "Default")
      (node (ref "C12") (pin "+") (pinfunction "+_+") (pintype "passive"))
      (node (ref "D4") (pin "A") (pinfunction "ANODE_A") (pintype "bidirectional"))
      (node (ref "L_MPPT") (pin "P$2") (pinfunction "P$2_P$2") (pintype "bidirectional"))
      (node (ref "R11") (pin "1") (pinfunction "1_1") (pintype "passive"))
    )
    (net (code "40") (name "Net-(D6-CATHODE)") (class "Default")
      (node (ref "D6") (pin "C") (pinfunction "CATHODE_C") (pintype "bidirectional"))
      (node (ref "L_5V") (pin "P$1") (pinfunction "P$1_P$1") (pintype "bidirectional"))
      (node (ref "U9") (pin "2") (pinfunction "OUT_2") (pintype "output"))
    )
    (net (code "41") (name "Net-(DIS1-LED_A_5V)") (class "Default")
      (node (ref "DIS1") (pin "15") (pinfunction "LED_A_5V_15") (pintype "bidirectional"))
      (node (ref "R19") (pin "1") (pinfunction "1_1") (pintype "passive"))
    )
    (net (code "42") (name "Net-(DIS1-LED_K)") (class "Default")
      (node (ref "DIS1") (pin "16") (pinfunction "LED_K_16") (pintype "bidirectional"))
      (node (ref "T1") (pin "C") (pinfunction "C_C") (pintype "passive"))
    )
    (net (code "43") (name "Net-(IC1-HO)") (class "Default")
      (node (ref "IC1") (pin "7") (pinfunction "HO_7") (pintype "bidirectional"))
      (node (ref "R8") (pin "2") (pinfunction "2_2") (pintype "passive"))
    )
    (net (code "44") (name "Net-(IC1-IN)") (class "Default")
      (node (ref "IC1") (pin "2") (pinfunction "IN_2") (pintype "bidirectional"))
      (node (ref "R7") (pin "2") (pinfunction "2_2") (pintype "passive"))
    )
    (net (code "45") (name "Net-(IC1-LO)") (class "Default")
      (node (ref "IC1") (pin "5") (pinfunction "LO_5") (pintype "bidirectional"))
      (node (ref "R9") (pin "2") (pinfunction "2_2") (pintype "passive"))
    )
    (net (code "46") (name "Net-(IC1-SD{slash})") (class "Default")
      (node (ref "IC1") (pin "3") (pinfunction "SD/_3") (pintype "bidirectional"))
      (node (ref "R6") (pin "2") (pinfunction "2_2") (pintype "passive"))
    )
    (net (code "47") (name "Net-(IC1-VB)") (class "Default")
      (node (ref "C10") (pin "1") (pinfunction "1_1") (pintype "passive"))
      (node (ref "D2") (pin "C") (pinfunction "C_C") (pintype "passive"))
      (node (ref "IC1") (pin "8") (pinfunction "VB_8") (pintype "power_in"))
    )
    (net (code "48") (name "Net-(IC1-VCC)") (class "Default")
      (node (ref "C5") (pin "1") (pinfunction "1_1") (pintype "passive"))
      (node (ref "C8") (pin "+") (pinfunction "+_+") (pintype "passive"))
      (node (ref "C9") (pin "2") (pinfunction "2_2") (pintype "passive"))
      (node (ref "D2") (pin "A") (pinfunction "A_A") (pintype "passive"))
      (node (ref "IC1") (pin "1") (pinfunction "VCC_1") (pintype "power_in"))
      (node (ref "R4") (pin "2") (pinfunction "2_2") (pintype "passive"))
      (node (ref "RS_S") (pin "2") (pinfunction "2_2") (pintype "passive"))
      (node (ref "U1") (pin "2") (pinfunction "S-_2") (pintype "input"))
      (node (ref "U4") (pin "5") (pinfunction "D_3_5") (pintype "passive"))
      (node (ref "U4") (pin "6") (pinfunction "D_2_6") (pintype "passive"))
      (node (ref "U4") (pin "7") (pinfunction "D_4_7") (pintype "passive"))
      (node (ref "U4") (pin "8") (pinfunction "D_8") (pintype "passive"))
    )
    (net (code "49") (name "Net-(IC1-VS)") (class "Default")
      (node (ref "C10") (pin "2") (pinfunction "2_2") (pintype "passive"))
      (node (ref "C11") (pin "1") (pinfunction "1_1") (pintype "passive"))
      (node (ref "D3") (pin "C") (pinfunction "C_C") (pintype "passive"))
      (node (ref "IC1") (pin "6") (pinfunction "VS_6") (pintype "power_in"))
      (node (ref "L_MPPT") (pin "P$1") (pinfunction "P$1_P$1") (pintype "bidirectional"))
      (node (ref "U4") (pin "1") (pinfunction "S_2_1") (pintype "passive"))
      (node (ref "U4") (pin "2") (pinfunction "S_3_2") (pintype "passive"))
      (node (ref "U4") (pin "3") (pinfunction "S_3") (pintype "passive"))
      (node (ref "U5") (pin "5") (pinfunction "D_3_5") (pintype "passive"))
      (node (ref "U5") (pin "6") (pinfunction "D_2_6") (pintype "passive"))
      (node (ref "U5") (pin "7") (pinfunction "D_4_7") (pintype "passive"))
      (node (ref "U5") (pin "8") (pinfunction "D_8") (pintype "passive"))
    )
    (net (code "50") (name "Net-(IC2-PA8)") (class "Default")
      (node (ref "IC2") (pin "29") (pinfunction "PA8_29") (pintype "bidirectional"))
      (node (ref "R10") (pin "1") (pinfunction "1_1") (pintype "passive"))
    )
    (net (code "51") (name "Net-(IC2-PA15)") (class "Default")
      (node (ref "IC2") (pin "38") (pinfunction "PA15_38") (pintype "bidirectional"))
      (node (ref "KEYPAD") (pin "7") (pinfunction "7_7") (pintype "passive"))
    )
    (net (code "52") (name "Net-(IC2-PB4)") (class "Default")
      (node (ref "IC2") (pin "40") (pinfunction "PB4_40") (pintype "bidirectional"))
      (node (ref "KEYPAD") (pin "6") (pinfunction "6_6") (pintype "passive"))
    )
    (net (code "53") (name "Net-(IC2-PB5)") (class "Default")
      (node (ref "IC2") (pin "41") (pinfunction "PB5_41") (pintype "bidirectional"))
      (node (ref "KEYPAD") (pin "5") (pinfunction "5_5") (pintype "passive"))
    )
    (net (code "54") (name "Net-(IC2-PB6)") (class "Default")
      (node (ref "IC2") (pin "42") (pinfunction "PB6_42") (pintype "bidirectional"))
      (node (ref "KEYPAD") (pin "4") (pinfunction "4_4") (pintype "passive"))
    )
    (net (code "55") (name "Net-(IC2-PB7)") (class "Default")
      (node (ref "IC2") (pin "43") (pinfunction "PB7_43") (pintype "bidirectional"))
      (node (ref "KEYPAD") (pin "3") (pinfunction "3_3") (pintype "passive"))
    )
    (net (code "56") (name "Net-(IC2-PB8)") (class "Default")
      (node (ref "IC2") (pin "45") (pinfunction "PB8_45") (pintype "bidirectional"))
      (node (ref "KEYPAD") (pin "2") (pinfunction "2_2") (pintype "passive"))
    )
    (net (code "57") (name "Net-(IC2-PB9)") (class "Default")
      (node (ref "IC2") (pin "46") (pinfunction "PB9_46") (pintype "bidirectional"))
      (node (ref "KEYPAD") (pin "1") (pinfunction "1_1") (pintype "passive"))
    )
    (net (code "58") (name "Net-(IC2-PC14_OSC32_IN)") (class "Default")
      (node (ref "C6") (pin "2") (pinfunction "2_2") (pintype "passive"))
      (node (ref "IC2") (pin "3") (pinfunction "PC14_OSC32_IN_3") (pintype "bidirectional"))
      (node (ref "Q1") (pin "1") (pinfunction "1_1") (pintype "passive"))
    )
    (net (code "59") (name "Net-(IC2-PC15_OSC32_OUT)") (class "Default")
      (node (ref "C7") (pin "2") (pinfunction "2_2") (pintype "passive"))
      (node (ref "IC2") (pin "4") (pinfunction "PC15_OSC32_OUT_4") (pintype "bidirectional"))
      (node (ref "Q1") (pin "4") (pinfunction "2_4") (pintype "passive"))
    )
    (net (code "60") (name "Net-(LED1-PadC)") (class "Default")
      (node (ref "LED1") (pin "C") (pinfunction "C_C") (pintype "passive"))
      (node (ref "R21") (pin "2") (pinfunction "2_2") (pintype "passive"))
    )
    (net (code "61") (name "Net-(R20-Pad2)") (class "Default")
      (node (ref "R20") (pin "2") (pinfunction "2_2") (pintype "passive"))
      (node (ref "T1") (pin "B") (pinfunction "B_B") (pintype "passive"))
    )
    (net (code "62") (name "Net-(R23-Pad1)") (class "Default")
      (node (ref "R23") (pin "1") (pinfunction "1_1") (pintype "passive"))
      (node (ref "R24") (pin "2") (pinfunction "2_2") (pintype "passive"))
      (node (ref "X1") (pin "2") (pinfunction "2_2") (pintype "passive"))
    )
    (net (code "63") (name "Net-(R25-Pad1)") (class "Default")
      (node (ref "R25") (pin "1") (pinfunction "1_1") (pintype "passive"))
      (node (ref "R26") (pin "2") (pinfunction "2_2") (pintype "passive"))
      (node (ref "X2") (pin "2") (pinfunction "2_2") (pintype "passive"))
    )
    (net (code "64") (name "Net-(R27-Pad1)") (class "Default")
      (node (ref "R27") (pin "1") (pinfunction "1_1") (pintype "passive"))
      (node (ref "R28") (pin "2") (pinfunction "2_2") (pintype "passive"))
      (node (ref "X1") (pin "3") (pinfunction "3_3") (pintype "passive"))
    )
    (net (code "65") (name "Net-(R29-Pad1)") (class "Default")
      (node (ref "R29") (pin "1") (pinfunction "1_1") (pintype "passive"))
      (node (ref "R30") (pin "2") (pinfunction "2_2") (pintype "passive"))
      (node (ref "X2") (pin "3") (pinfunction "3_3") (pintype "passive"))
    )
    (net (code "66") (name "Net-(R31-Pad1)") (class "Default")
      (node (ref "R31") (pin "1") (pinfunction "1_1") (pintype "passive"))
      (node (ref "R32") (pin "2") (pinfunction "2_2") (pintype "passive"))
      (node (ref "X3") (pin "2") (pinfunction "2_2") (pintype "passive"))
    )
    (net (code "67") (name "Net-(R33-Pad1)") (class "Default")
      (node (ref "R33") (pin "1") (pinfunction "1_1") (pintype "passive"))
      (node (ref "R34") (pin "2") (pinfunction "2_2") (pintype "passive"))
      (node (ref "X4") (pin "2") (pinfunction "2_2") (pintype "passive"))
    )
    (net (code "68") (name "Net-(R35-Pad1)") (class "Default")
      (node (ref "R35") (pin "1") (pinfunction "1_1") (pintype "passive"))
      (node (ref "R36") (pin "2") (pinfunction "2_2") (pintype "passive"))
      (node (ref "X3") (pin "3") (pinfunction "3_3") (pintype "passive"))
    )
    (net (code "69") (name "Net-(R37-Pad1)") (class "Default")
      (node (ref "R37") (pin "1") (pinfunction "1_1") (pintype "passive"))
      (node (ref "R38") (pin "2") (pinfunction "2_2") (pintype "passive"))
      (node (ref "X4") (pin "3") (pinfunction "3_3") (pintype "passive"))
    )
    (net (code "70") (name "Net-(U1-S+)") (class "Default")
      (node (ref "RS_S") (pin "1") (pinfunction "1_1") (pintype "passive"))
      (node (ref "SOL") (pin "3") (pinfunction "3_3") (pintype "passive"))
      (node (ref "U1") (pin "3") (pinfunction "S+_3") (pintype "input"))
    )
    (net (code "71") (name "Net-(U2-S)") (class "Default")
      (node (ref "U2") (pin "2") (pinfunction "S_2") (pintype "passive"))
      (node (ref "U3") (pin "3") (pinfunction "D_3") (pintype "output"))
    )
    (net (code "72") (name "Net-(U3-G)") (class "Default")
      (node (ref "C4") (pin "2") (pinfunction "2_2") (pintype "passive"))
      (node (ref "R3") (pin "2") (pinfunction "2_2") (pintype "passive"))
      (node (ref "U3") (pin "1") (pinfunction "G_1") (pintype "input"))
    )
    (net (code "73") (name "Net-(U4-G)") (class "Default")
      (node (ref "R8") (pin "1") (pinfunction "1_1") (pintype "passive"))
      (node (ref "U4") (pin "4") (pinfunction "G_4") (pintype "passive"))
    )
    (net (code "74") (name "Net-(U5-G)") (class "Default")
      (node (ref "R9") (pin "1") (pinfunction "1_1") (pintype "passive"))
      (node (ref "U5") (pin "4") (pinfunction "G_4") (pintype "passive"))
    )
    (net (code "75") (name "Net-(U6-G)") (class "Default")
      (node (ref "R10") (pin "2") (pinfunction "2_2") (pintype "passive"))
      (node (ref "U6") (pin "1") (pinfunction "G_1") (pintype "input"))
    )
    (net (code "76") (name "Net-(U7-IN+)") (class "Default")
      (node (ref "C17") (pin "2") (pinfunction "2_2") (pintype "passive"))
      (node (ref "R17") (pin "1") (pinfunction "1_1") (pintype "passive"))
      (node (ref "U7") (pin "4") (pinfunction "IN+_4") (pintype "input"))
    )
    (net (code "77") (name "Net-(U7-IN-)") (class "Default")
      (node (ref "C17") (pin "1") (pinfunction "1_1") (pintype "passive"))
      (node (ref "R18") (pin "1") (pinfunction "1_1") (pintype "passive"))
      (node (ref "U7") (pin "5") (pinfunction "IN-_5") (pintype "input"))
    )
    (net (code "78") (name "Net-(U7-REF)") (class "Default")
      (node (ref "R15") (pin "1") (pinfunction "1_1") (pintype "passive"))
      (node (ref "R16") (pin "2") (pinfunction "2_2") (pintype "passive"))
      (node (ref "U7") (pin "1") (pinfunction "REF_1") (pintype "input"))
    )
    (net (code "79") (name "Net-(U10-D)") (class "Default")
      (node (ref "D7") (pin "A") (pinfunction "A_A") (pintype "passive"))
      (node (ref "U$2") (pin "COIL+") (pinfunction "COIL+_COIL+") (pintype "bidirectional"))
      (node (ref "U10") (pin "3") (pinfunction "D_3") (pintype "output"))
    )
    (net (code "80") (name "Net-(U10-G)") (class "Default")
      (node (ref "R22") (pin "2") (pinfunction "2_2") (pintype "passive"))
      (node (ref "U10") (pin "1") (pinfunction "G_1") (pintype "input"))
    )
    (net (code "81") (name "unconnected-(IC2-PA11-Pad32)") (class "Default")
      (node (ref "IC2") (pin "32") (pinfunction "PA11_32") (pintype "bidirectional"))
    )
    (net (code "82") (name "unconnected-(IC2-PC13-Pad2)") (class "Default")
      (node (ref "IC2") (pin "2") (pinfunction "PC13_2") (pintype "bidirectional"))
    )
    (net (code "83") (name "unconnected-(IC2-PF0_OSC_IN-Pad5)") (class "Default")
      (node (ref "IC2") (pin "5") (pinfunction "PF0_OSC_IN_5") (pintype "bidirectional"))
    )
    (net (code "84") (name "unconnected-(IC2-PF1_OSC_OUT-Pad6)") (class "Default")
      (node (ref "IC2") (pin "6") (pinfunction "PF1_OSC_OUT_6") (pintype "input"))
    )
    (net (code "85") (name "unconnected-(U$2-NC-PadNC@1)") (class "Default")
      (node (ref "U$2") (pin "NC@1") (pinfunction "NC_NC@1") (pintype "bidirectional"))
    )
    (net (code "86") (name "unconnected-(U$2-NC-PadNC@2)") (class "Default")
      (node (ref "U$2") (pin "NC@2") (pinfunction "NC_NC@2") (pintype "bidirectional"))
    )
    (net (code "87") (name "unconnected-(U$2-PadCOIL-)") (class "Default")
      (node (ref "U$2") (pin "COIL-") (pinfunction "COIL-_COIL-") (pintype "bidirectional"))
    )
  )
)
